# 18650_1S3P.net
KiCad netlist of a schematic drawn in EAGLE
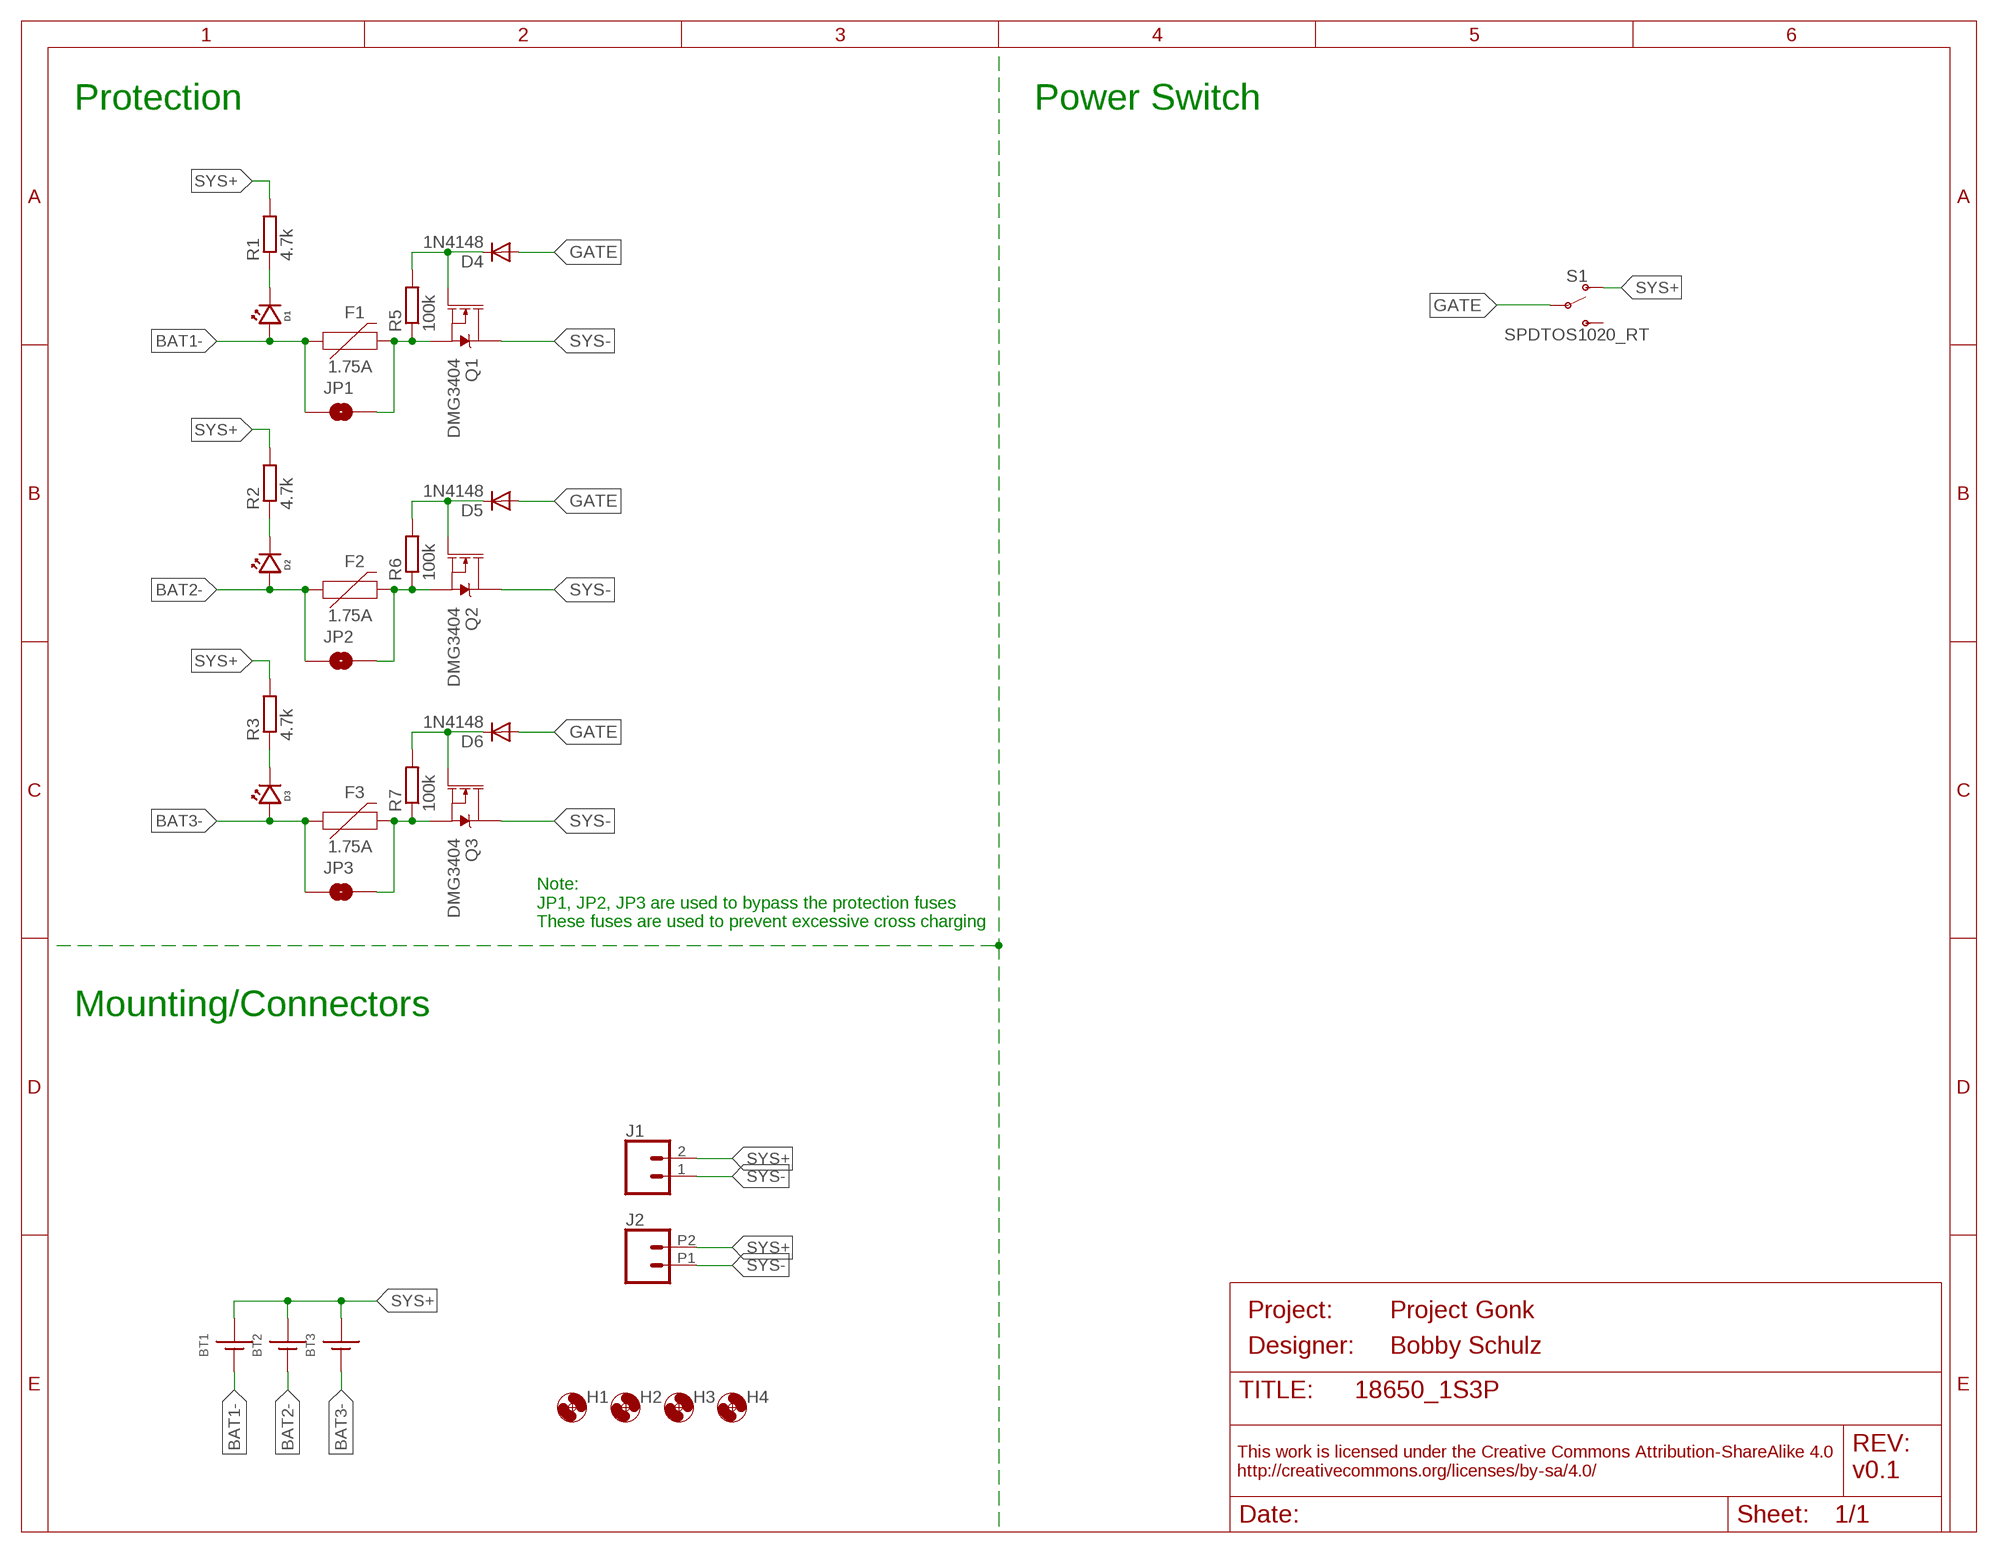
[diagram p0: schematic, sheet 1]

(export (version "E")
  (design (tool "Eeschema 10.0.6"))
  (components
    (comp (ref "BT1")
      (value "18650NO_PROTEC")
      (footprint "eagle-import:BATT_18650_CLIP")
      (fields (field (name "MF") "Keystone") (field (name "MPN") "54"))
      (libsource (lib "eagle-import") (part "18650NO_PROTEC"))
    )
    (comp (ref "BT2")
      (value "18650NO_PROTEC")
      (footprint "eagle-import:BATT_18650_CLIP")
      (fields (field (name "MF") "Keystone") (field (name "MPN") "54"))
      (libsource (lib "eagle-import") (part "18650NO_PROTEC"))
    )
    (comp (ref "BT3")
      (value "18650NO_PROTEC")
      (footprint "eagle-import:BATT_18650_CLIP")
      (fields (field (name "MF") "Keystone") (field (name "MPN") "54"))
      (libsource (lib "eagle-import") (part "18650NO_PROTEC"))
    )
    (comp (ref "D1")
      (value "LED0805")
      (footprint "eagle-import:LED_0805")
      (fields (field (name "MF") "OSRAM") (field (name "MPN") "LS R976-NR-1"))
      (libsource (lib "eagle-import") (part "LED0805"))
    )
    (comp (ref "D2")
      (value "LED0805")
      (footprint "eagle-import:LED_0805")
      (fields (field (name "MF") "OSRAM") (field (name "MPN") "LS R976-NR-1"))
      (libsource (lib "eagle-import") (part "LED0805"))
    )
    (comp (ref "D3")
      (value "LED0805")
      (footprint "eagle-import:LED_0805")
      (fields (field (name "MF") "OSRAM") (field (name "MPN") "LS R976-NR-1"))
      (libsource (lib "eagle-import") (part "LED0805"))
    )
    (comp (ref "D4")
      (value "1N4148")
      (footprint "eagle-import:SOD323-R")
      (fields
        (field (name "DIGIKEY") "1N4148WS-FDICT-ND")
        (field (name "MF") "Diodes Inc")
        (field (name "MPN") "1N4148WS-7-F")
      )
      (libsource (lib "eagle-import") (part "DIODESOD-323"))
    )
    (comp (ref "D5")
      (value "1N4148")
      (footprint "eagle-import:SOD323-R")
      (fields
        (field (name "DIGIKEY") "1N4148WS-FDICT-ND")
        (field (name "MF") "Diodes Inc")
        (field (name "MPN") "1N4148WS-7-F")
      )
      (libsource (lib "eagle-import") (part "DIODESOD-323"))
    )
    (comp (ref "D6")
      (value "1N4148")
      (footprint "eagle-import:SOD323-R")
      (fields
        (field (name "DIGIKEY") "1N4148WS-FDICT-ND")
        (field (name "MF") "Diodes Inc")
        (field (name "MPN") "1N4148WS-7-F")
      )
      (libsource (lib "eagle-import") (part "DIODESOD-323"))
    )
    (comp (ref "F1")
      (value "1.75A")
      (footprint "eagle-import:1210_BOURNS")
      (fields (field (name "MF") "Bourns") (field (name "MPN") "MF-USMF175X-2"))
      (libsource (lib "eagle-import") (part "PPTC12101.75A"))
    )
    (comp (ref "F2")
      (value "1.75A")
      (footprint "eagle-import:1210_BOURNS")
      (fields (field (name "MF") "Bourns") (field (name "MPN") "MF-USMF175X-2"))
      (libsource (lib "eagle-import") (part "PPTC12101.75A"))
    )
    (comp (ref "F3")
      (value "1.75A")
      (footprint "eagle-import:1210_BOURNS")
      (fields (field (name "MF") "Bourns") (field (name "MPN") "MF-USMF175X-2"))
      (libsource (lib "eagle-import") (part "PPTC12101.75A"))
    )
    (comp (ref "H1")
      (value "MOUNTING_HOLE4_NP")
      (footprint "eagle-import:4_40")
      (libsource (lib "eagle-import") (part "MOUNTING_HOLE4_NP"))
    )
    (comp (ref "H2")
      (value "MOUNTING_HOLE4_NP")
      (footprint "eagle-import:4_40")
      (libsource (lib "eagle-import") (part "MOUNTING_HOLE4_NP"))
    )
    (comp (ref "H3")
      (value "MOUNTING_HOLE4_NP")
      (footprint "eagle-import:4_40")
      (libsource (lib "eagle-import") (part "MOUNTING_HOLE4_NP"))
    )
    (comp (ref "H4")
      (value "MOUNTING_HOLE4_NP")
      (footprint "eagle-import:4_40")
      (libsource (lib "eagle-import") (part "MOUNTING_HOLE4_NP"))
    )
    (comp (ref "J1")
      (value "CONN_023.5MM_ROUND_RESTRICT")
      (footprint "eagle-import:SCREWTERMINAL-3.5MM-2_ROUND_RESTRICT")
      (fields (field (name "MF") "On Shore") (field (name "MPN") "OSTTE020161"))
      (libsource (lib "eagle-import") (part "CONN_023.5MM_ROUND_RESTRICT"))
    )
    (comp (ref "J2")
      (value "CONN_022.54_SCREW_ROUND")
      (footprint "eagle-import:1X02_2.54_SCREWTERM_ROUND")
      (fields (field (name "MF") "OnShore") (field (name "MPN") "OSTVN02A150"))
      (libsource (lib "eagle-import") (part "CONN_022.54_SCREW_ROUND"))
    )
    (comp (ref "JP1")
      (value "JUMPER-SMT_2_NO_SILK")
      (footprint "eagle-import:SMT-JUMPER_2_NO_SILK")
      (libsource (lib "eagle-import") (part "JUMPER-SMT_2_NO_SILK"))
    )
    (comp (ref "JP2")
      (value "JUMPER-SMT_2_NO_SILK")
      (footprint "eagle-import:SMT-JUMPER_2_NO_SILK")
      (libsource (lib "eagle-import") (part "JUMPER-SMT_2_NO_SILK"))
    )
    (comp (ref "JP3")
      (value "JUMPER-SMT_2_NO_SILK")
      (footprint "eagle-import:SMT-JUMPER_2_NO_SILK")
      (libsource (lib "eagle-import") (part "JUMPER-SMT_2_NO_SILK"))
    )
    (comp (ref "Q1")
      (value "DMG3404")
      (footprint "eagle-import:SOT23-3")
      (fields (field (name "MF") "Diodes Incorporated") (field (name "MPN") "DMG3404L-7"))
      (libsource (lib "eagle-import") (part "MOSFET-NCH-DMG3404L"))
    )
    (comp (ref "Q2")
      (value "DMG3404")
      (footprint "eagle-import:SOT23-3")
      (fields (field (name "MF") "Diodes Incorporated") (field (name "MPN") "DMG3404L-7"))
      (libsource (lib "eagle-import") (part "MOSFET-NCH-DMG3404L"))
    )
    (comp (ref "Q3")
      (value "DMG3404")
      (footprint "eagle-import:SOT23-3")
      (fields (field (name "MF") "Diodes Incorporated") (field (name "MPN") "DMG3404L-7"))
      (libsource (lib "eagle-import") (part "MOSFET-NCH-DMG3404L"))
    )
    (comp (ref "R1")
      (value "4.7k")
      (footprint "eagle-import:R0603")
      (fields (field (name "MF") "Yageo") (field (name "MPN") "RC0603FR-074K7L"))
      (libsource (lib "eagle-import") (part "R-EU_R06034.7K"))
    )
    (comp (ref "R2")
      (value "4.7k")
      (footprint "eagle-import:R0603")
      (fields (field (name "MF") "Yageo") (field (name "MPN") "RC0603FR-074K7L"))
      (libsource (lib "eagle-import") (part "R-EU_R06034.7K"))
    )
    (comp (ref "R3")
      (value "4.7k")
      (footprint "eagle-import:R0603")
      (fields (field (name "MF") "Yageo") (field (name "MPN") "RC0603FR-074K7L"))
      (libsource (lib "eagle-import") (part "R-EU_R06034.7K"))
    )
    (comp (ref "R5")
      (value "100k")
      (footprint "eagle-import:R0603")
      (fields (field (name "MF") "Yageo") (field (name "MPN") "RC0603FR-07100KL"))
      (libsource (lib "eagle-import") (part "R-EU_R0603100K"))
    )
    (comp (ref "R6")
      (value "100k")
      (footprint "eagle-import:R0603")
      (fields (field (name "MF") "Yageo") (field (name "MPN") "RC0603FR-07100KL"))
      (libsource (lib "eagle-import") (part "R-EU_R0603100K"))
    )
    (comp (ref "R7")
      (value "100k")
      (footprint "eagle-import:R0603")
      (fields (field (name "MF") "Yageo") (field (name "MPN") "RC0603FR-07100KL"))
      (libsource (lib "eagle-import") (part "R-EU_R0603100K"))
    )
    (comp (ref "S1")
      (value "SPDTOS1020_RT")
      (footprint "eagle-import:OS102011MA1QN1")
      (fields (field (name "MF") "C&K") (field (name "MPN") "OS102011MA1QN1"))
      (libsource (lib "eagle-import") (part "SPDTOS1020_RT"))
    )
  )
  (nets
    (net (code "1") (name "BAT1-") (class "Default")
      (node (ref "BT1") (pin "BATT-@1") (pinfunction "-_BATT-@1") (pintype "bidirectional"))
      (node (ref "BT1") (pin "BATT-@2") (pinfunction "-_BATT-@2") (pintype "bidirectional"))
      (node (ref "BT1") (pin "BATT-@3") (pinfunction "-_BATT-@3") (pintype "bidirectional"))
      (node (ref "D1") (pin "ANODE") (pinfunction "ANODE_ANODE") (pintype "power_in"))
      (node (ref "F1") (pin "1") (pinfunction "1_1") (pintype "bidirectional"))
      (node (ref "JP1") (pin "1") (pinfunction "1_1") (pintype "passive"))
    )
    (net (code "2") (name "BAT2-") (class "Default")
      (node (ref "BT2") (pin "BATT-@1") (pinfunction "-_BATT-@1") (pintype "bidirectional"))
      (node (ref "BT2") (pin "BATT-@2") (pinfunction "-_BATT-@2") (pintype "bidirectional"))
      (node (ref "BT2") (pin "BATT-@3") (pinfunction "-_BATT-@3") (pintype "bidirectional"))
      (node (ref "D2") (pin "ANODE") (pinfunction "ANODE_ANODE") (pintype "power_in"))
      (node (ref "F2") (pin "1") (pinfunction "1_1") (pintype "bidirectional"))
      (node (ref "JP2") (pin "1") (pinfunction "1_1") (pintype "passive"))
    )
    (net (code "3") (name "BAT3-") (class "Default")
      (node (ref "BT3") (pin "BATT-@1") (pinfunction "-_BATT-@1") (pintype "bidirectional"))
      (node (ref "BT3") (pin "BATT-@2") (pinfunction "-_BATT-@2") (pintype "bidirectional"))
      (node (ref "BT3") (pin "BATT-@3") (pinfunction "-_BATT-@3") (pintype "bidirectional"))
      (node (ref "D3") (pin "ANODE") (pinfunction "ANODE_ANODE") (pintype "power_in"))
      (node (ref "F3") (pin "1") (pinfunction "1_1") (pintype "bidirectional"))
      (node (ref "JP3") (pin "1") (pinfunction "1_1") (pintype "passive"))
    )
    (net (code "4") (name "GATE") (class "Default")
      (node (ref "D4") (pin "A") (pinfunction "A_A") (pintype "passive"))
      (node (ref "D5") (pin "A") (pinfunction "A_A") (pintype "passive"))
      (node (ref "D6") (pin "A") (pinfunction "A_A") (pintype "passive"))
      (node (ref "S1") (pin "2") (pinfunction "P_2") (pintype "passive"))
    )
    (net (code "5") (name "Net-(D1-PadCATHODE)") (class "Default")
      (node (ref "D1") (pin "CATHODE") (pinfunction "CATHODE_CATHODE") (pintype "power_in"))
      (node (ref "R1") (pin "1") (pinfunction "1_1") (pintype "passive"))
    )
    (net (code "6") (name "Net-(D2-PadCATHODE)") (class "Default")
      (node (ref "D2") (pin "CATHODE") (pinfunction "CATHODE_CATHODE") (pintype "power_in"))
      (node (ref "R2") (pin "1") (pinfunction "1_1") (pintype "passive"))
    )
    (net (code "7") (name "Net-(D3-PadCATHODE)") (class "Default")
      (node (ref "D3") (pin "CATHODE") (pinfunction "CATHODE_CATHODE") (pintype "power_in"))
      (node (ref "R3") (pin "1") (pinfunction "1_1") (pintype "passive"))
    )
    (net (code "8") (name "Net-(Q1-G)") (class "Default")
      (node (ref "D4") (pin "C") (pinfunction "C_C") (pintype "passive"))
      (node (ref "Q1") (pin "1") (pinfunction "G_1") (pintype "bidirectional"))
      (node (ref "R5") (pin "2") (pinfunction "2_2") (pintype "passive"))
    )
    (net (code "9") (name "Net-(Q1-S)") (class "Default")
      (node (ref "F1") (pin "2") (pinfunction "2_2") (pintype "bidirectional"))
      (node (ref "JP1") (pin "2") (pinfunction "2_2") (pintype "passive"))
      (node (ref "Q1") (pin "2") (pinfunction "S_2") (pintype "bidirectional"))
      (node (ref "R5") (pin "1") (pinfunction "1_1") (pintype "passive"))
    )
    (net (code "10") (name "Net-(Q2-G)") (class "Default")
      (node (ref "D5") (pin "C") (pinfunction "C_C") (pintype "passive"))
      (node (ref "Q2") (pin "1") (pinfunction "G_1") (pintype "bidirectional"))
      (node (ref "R6") (pin "2") (pinfunction "2_2") (pintype "passive"))
    )
    (net (code "11") (name "Net-(Q2-S)") (class "Default")
      (node (ref "F2") (pin "2") (pinfunction "2_2") (pintype "bidirectional"))
      (node (ref "JP2") (pin "2") (pinfunction "2_2") (pintype "passive"))
      (node (ref "Q2") (pin "2") (pinfunction "S_2") (pintype "bidirectional"))
      (node (ref "R6") (pin "1") (pinfunction "1_1") (pintype "passive"))
    )
    (net (code "12") (name "Net-(Q3-G)") (class "Default")
      (node (ref "D6") (pin "C") (pinfunction "C_C") (pintype "passive"))
      (node (ref "Q3") (pin "1") (pinfunction "G_1") (pintype "bidirectional"))
      (node (ref "R7") (pin "2") (pinfunction "2_2") (pintype "passive"))
    )
    (net (code "13") (name "Net-(Q3-S)") (class "Default")
      (node (ref "F3") (pin "2") (pinfunction "2_2") (pintype "bidirectional"))
      (node (ref "JP3") (pin "2") (pinfunction "2_2") (pintype "passive"))
      (node (ref "Q3") (pin "2") (pinfunction "S_2") (pintype "bidirectional"))
      (node (ref "R7") (pin "1") (pinfunction "1_1") (pintype "passive"))
    )
    (net (code "14") (name "SYS+") (class "Default")
      (node (ref "BT1") (pin "BATT+@1") (pinfunction "+_BATT+@1") (pintype "bidirectional"))
      (node (ref "BT1") (pin "BATT+@2") (pinfunction "+_BATT+@2") (pintype "bidirectional"))
      (node (ref "BT1") (pin "BATT+@3") (pinfunction "+_BATT+@3") (pintype "bidirectional"))
      (node (ref "BT2") (pin "BATT+@1") (pinfunction "+_BATT+@1") (pintype "bidirectional"))
      (node (ref "BT2") (pin "BATT+@2") (pinfunction "+_BATT+@2") (pintype "bidirectional"))
      (node (ref "BT2") (pin "BATT+@3") (pinfunction "+_BATT+@3") (pintype "bidirectional"))
      (node (ref "BT3") (pin "BATT+@1") (pinfunction "+_BATT+@1") (pintype "bidirectional"))
      (node (ref "BT3") (pin "BATT+@2") (pinfunction "+_BATT+@2") (pintype "bidirectional"))
      (node (ref "BT3") (pin "BATT+@3") (pinfunction "+_BATT+@3") (pintype "bidirectional"))
      (node (ref "J1") (pin "2") (pinfunction "2_2") (pintype "passive"))
      (node (ref "J2") (pin "P2") (pinfunction "2_P2") (pintype "passive"))
      (node (ref "R1") (pin "2") (pinfunction "2_2") (pintype "passive"))
      (node (ref "R2") (pin "2") (pinfunction "2_2") (pintype "passive"))
      (node (ref "R3") (pin "2") (pinfunction "2_2") (pintype "passive"))
      (node (ref "S1") (pin "1") (pinfunction "O_1") (pintype "passive"))
    )
    (net (code "15") (name "SYS-") (class "Default")
      (node (ref "J1") (pin "1") (pinfunction "1_1") (pintype "passive"))
      (node (ref "J2") (pin "P1") (pinfunction "1_P1") (pintype "passive"))
      (node (ref "Q1") (pin "3") (pinfunction "D_3") (pintype "bidirectional"))
      (node (ref "Q2") (pin "3") (pinfunction "D_3") (pintype "bidirectional"))
      (node (ref "Q3") (pin "3") (pinfunction "D_3") (pintype "bidirectional"))
    )
    (net (code "16") (name "unconnected-(S1-S-Pad3)") (class "Default")
      (node (ref "S1") (pin "3") (pinfunction "S_3") (pintype "passive"))
    )
  )
)
